# vcf_leiter.net
KiCad netlist of a schematic drawn in EAGLE
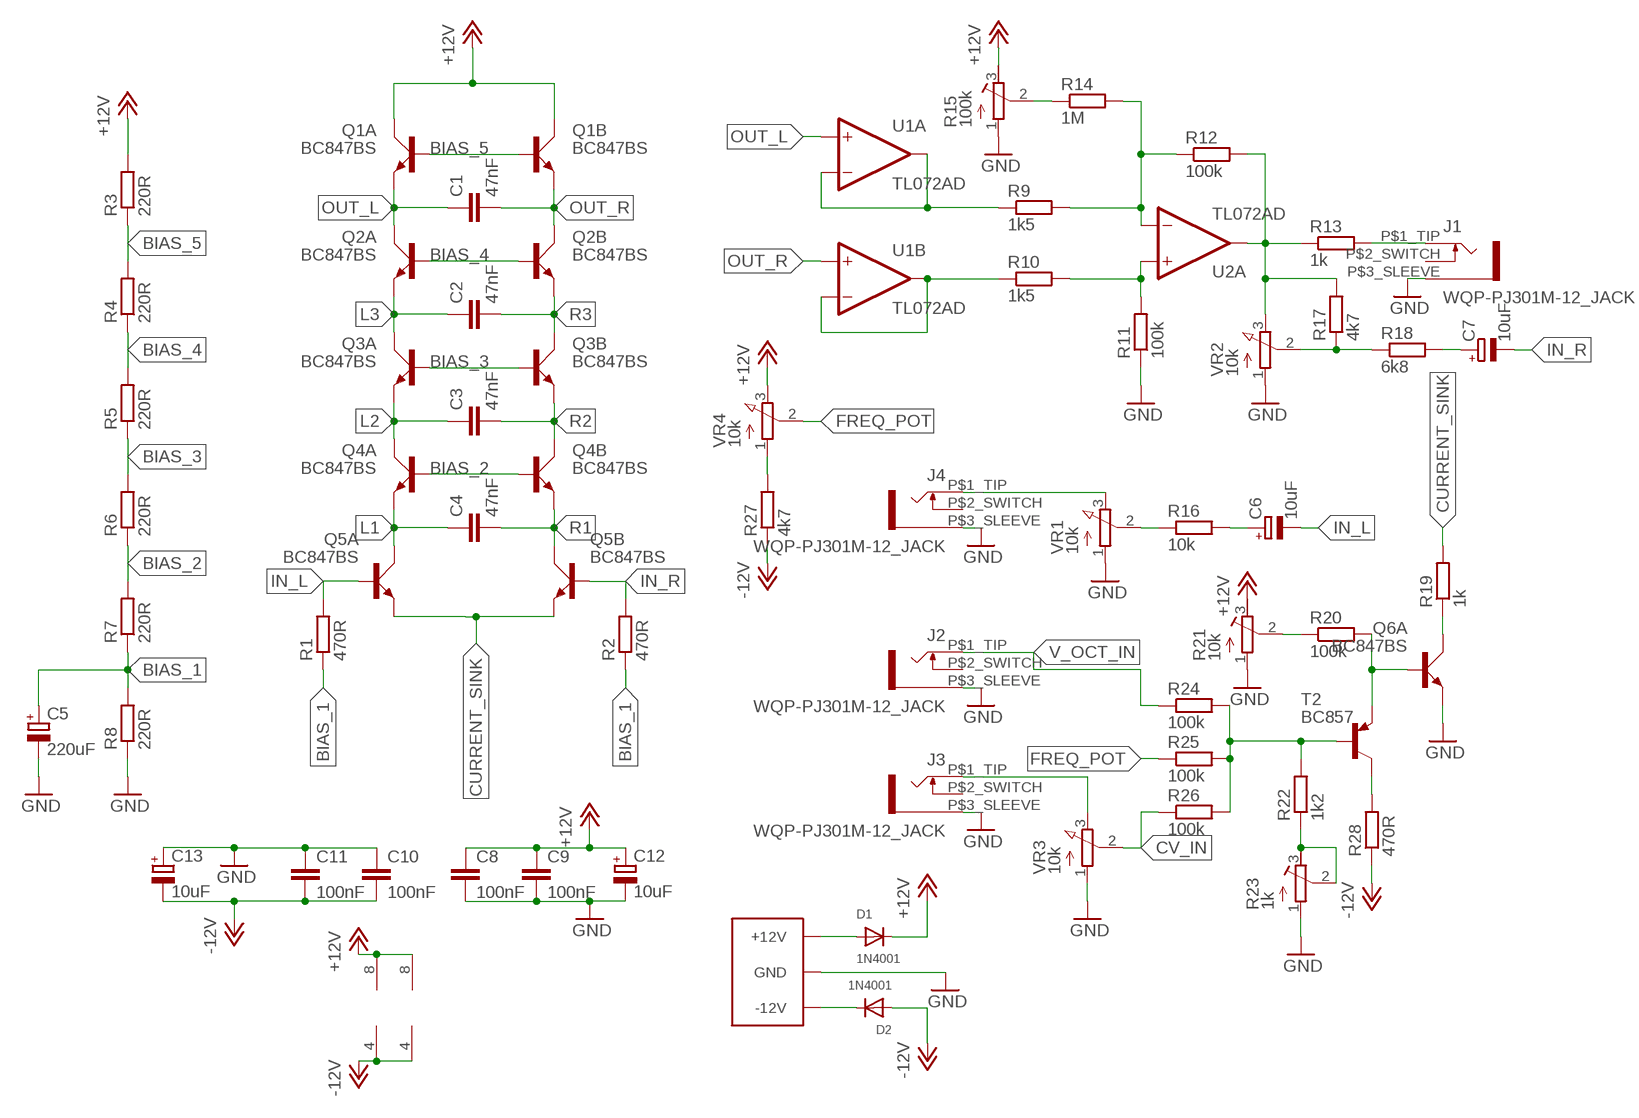
[diagram p0: schematic, sheet 1]

(export (version "E")
  (design (tool "Eeschema 10.0.6"))
  (components
    (comp (ref "C1")
      (value "47nF")
      (footprint "eagle-import:C0402")
      (libsource (lib "eagle-import") (part "C-EUC0402"))
    )
    (comp (ref "C2")
      (value "47nF")
      (footprint "eagle-import:C0402")
      (libsource (lib "eagle-import") (part "C-EUC0402"))
    )
    (comp (ref "C3")
      (value "47nF")
      (footprint "eagle-import:C0402")
      (libsource (lib "eagle-import") (part "C-EUC0402"))
    )
    (comp (ref "C4")
      (value "47nF")
      (footprint "eagle-import:C0402")
      (libsource (lib "eagle-import") (part "C-EUC0402"))
    )
    (comp (ref "C5")
      (value "220uF")
      (footprint "eagle-import:PANASONIC_C")
      (libsource (lib "eagle-import") (part "CPOL-EUC"))
    )
    (comp (ref "C6")
      (value "10uF")
      (footprint "eagle-import:PANASONIC_C")
      (libsource (lib "eagle-import") (part "CPOL-EUC"))
    )
    (comp (ref "C7")
      (value "10uF")
      (footprint "eagle-import:PANASONIC_C")
      (libsource (lib "eagle-import") (part "CPOL-EUC"))
    )
    (comp (ref "C8")
      (value "100nF")
      (footprint "eagle-import:C0402")
      (libsource (lib "eagle-import") (part "C-EUC0402"))
    )
    (comp (ref "C9")
      (value "100nF")
      (footprint "eagle-import:C0402")
      (libsource (lib "eagle-import") (part "C-EUC0402"))
    )
    (comp (ref "C10")
      (value "100nF")
      (footprint "eagle-import:C0402")
      (libsource (lib "eagle-import") (part "C-EUC0402"))
    )
    (comp (ref "C11")
      (value "100nF")
      (footprint "eagle-import:C0402")
      (libsource (lib "eagle-import") (part "C-EUC0402"))
    )
    (comp (ref "C12")
      (value "10uF")
      (footprint "eagle-import:PANASONIC_C")
      (libsource (lib "eagle-import") (part "CPOL-EUC"))
    )
    (comp (ref "C13")
      (value "10uF")
      (footprint "eagle-import:PANASONIC_C")
      (libsource (lib "eagle-import") (part "CPOL-EUC"))
    )
    (comp (ref "C14")
      (value "EURO_POWER_LOCKFAT-LOCK")
      (footprint "eagle-import:EURO_PWR_HEADER_LOCK")
      (libsource (lib "eagle-import") (part "EURO_POWER_LOCKFAT-LOCK"))
    )
    (comp (ref "D1")
      (value "1N4001")
      (footprint "eagle-import:SMADIODE")
      (libsource (lib "eagle-import") (part "DIODESMA"))
    )
    (comp (ref "D2")
      (value "1N4001")
      (footprint "eagle-import:SMADIODE")
      (libsource (lib "eagle-import") (part "DIODESMA"))
    )
    (comp (ref "J1")
      (value "WQP-PJ301M-12_JACK")
      (footprint "eagle-import:WQP-PJ301M-12_JACK")
      (libsource (lib "eagle-import") (part "WQP-PJ301M-12_JACK"))
    )
    (comp (ref "J2")
      (value "WQP-PJ301M-12_JACK")
      (footprint "eagle-import:WQP-PJ301M-12_JACK")
      (libsource (lib "eagle-import") (part "WQP-PJ301M-12_JACK"))
    )
    (comp (ref "J3")
      (value "WQP-PJ301M-12_JACK")
      (footprint "eagle-import:WQP-PJ301M-12_JACK")
      (libsource (lib "eagle-import") (part "WQP-PJ301M-12_JACK"))
    )
    (comp (ref "J4")
      (value "WQP-PJ301M-12_JACK")
      (footprint "eagle-import:WQP-PJ301M-12_JACK")
      (libsource (lib "eagle-import") (part "WQP-PJ301M-12_JACK"))
    )
    (comp (ref "Q1")
      (value "BC847BS")
      (footprint "eagle-import:SOT363_PHILIPS")
      (libsource (lib "eagle-import") (part "BC847BS"))
    )
    (comp (ref "Q2")
      (value "BC847BS")
      (footprint "eagle-import:SOT363_PHILIPS")
      (libsource (lib "eagle-import") (part "BC847BS"))
    )
    (comp (ref "Q3")
      (value "BC847BS")
      (footprint "eagle-import:SOT363_PHILIPS")
      (libsource (lib "eagle-import") (part "BC847BS"))
    )
    (comp (ref "Q4")
      (value "BC847BS")
      (footprint "eagle-import:SOT363_PHILIPS")
      (libsource (lib "eagle-import") (part "BC847BS"))
    )
    (comp (ref "Q5")
      (value "BC847BS")
      (footprint "eagle-import:SOT363_PHILIPS")
      (libsource (lib "eagle-import") (part "BC847BS"))
    )
    (comp (ref "Q6")
      (value "BC847BS")
      (footprint "eagle-import:SOT363_PHILIPS")
      (libsource (lib "eagle-import") (part "BC847BS"))
    )
    (comp (ref "R1")
      (value "470R")
      (footprint "eagle-import:R0402")
      (libsource (lib "eagle-import") (part "R-EU_R0402"))
    )
    (comp (ref "R2")
      (value "470R")
      (footprint "eagle-import:R0402")
      (libsource (lib "eagle-import") (part "R-EU_R0402"))
    )
    (comp (ref "R3")
      (value "220R")
      (footprint "eagle-import:R0402")
      (libsource (lib "eagle-import") (part "R-EU_R0402"))
    )
    (comp (ref "R4")
      (value "220R")
      (footprint "eagle-import:R0402")
      (libsource (lib "eagle-import") (part "R-EU_R0402"))
    )
    (comp (ref "R5")
      (value "220R")
      (footprint "eagle-import:R0402")
      (libsource (lib "eagle-import") (part "R-EU_R0402"))
    )
    (comp (ref "R6")
      (value "220R")
      (footprint "eagle-import:R0402")
      (libsource (lib "eagle-import") (part "R-EU_R0402"))
    )
    (comp (ref "R7")
      (value "220R")
      (footprint "eagle-import:R0402")
      (libsource (lib "eagle-import") (part "R-EU_R0402"))
    )
    (comp (ref "R8")
      (value "220R")
      (footprint "eagle-import:R0402")
      (libsource (lib "eagle-import") (part "R-EU_R0402"))
    )
    (comp (ref "R9")
      (value "1k5")
      (footprint "eagle-import:R0402")
      (libsource (lib "eagle-import") (part "R-EU_R0402"))
    )
    (comp (ref "R10")
      (value "1k5")
      (footprint "eagle-import:R0402")
      (libsource (lib "eagle-import") (part "R-EU_R0402"))
    )
    (comp (ref "R11")
      (value "100k")
      (footprint "eagle-import:R0402")
      (libsource (lib "eagle-import") (part "R-EU_R0402"))
    )
    (comp (ref "R12")
      (value "100k")
      (footprint "eagle-import:R0402")
      (libsource (lib "eagle-import") (part "R-EU_R0402"))
    )
    (comp (ref "R13")
      (value "1k")
      (footprint "eagle-import:R0402")
      (libsource (lib "eagle-import") (part "R-EU_R0402"))
    )
    (comp (ref "R14")
      (value "1M")
      (footprint "eagle-import:R0402")
      (libsource (lib "eagle-import") (part "R-EU_R0402"))
    )
    (comp (ref "R15")
      (value "100k")
      (footprint "eagle-import:RTRIM64W")
      (libsource (lib "eagle-import") (part "R-TRIMM64W"))
    )
    (comp (ref "R16")
      (value "10k")
      (footprint "eagle-import:R0402")
      (libsource (lib "eagle-import") (part "R-EU_R0402"))
    )
    (comp (ref "R17")
      (value "4k7")
      (footprint "eagle-import:R0402")
      (libsource (lib "eagle-import") (part "R-EU_R0402"))
    )
    (comp (ref "R18")
      (value "6k8")
      (footprint "eagle-import:R0402")
      (libsource (lib "eagle-import") (part "R-EU_R0402"))
    )
    (comp (ref "R19")
      (value "1k")
      (footprint "eagle-import:R0402")
      (libsource (lib "eagle-import") (part "R-EU_R0402"))
    )
    (comp (ref "R20")
      (value "100k")
      (footprint "eagle-import:R0402")
      (libsource (lib "eagle-import") (part "R-EU_R0402"))
    )
    (comp (ref "R21")
      (value "10k")
      (footprint "eagle-import:RTRIM64W")
      (libsource (lib "eagle-import") (part "R-TRIMM64W"))
    )
    (comp (ref "R22")
      (value "1k2")
      (footprint "eagle-import:R0402")
      (libsource (lib "eagle-import") (part "R-EU_R0402"))
    )
    (comp (ref "R23")
      (value "1k")
      (footprint "eagle-import:RTRIM64W")
      (libsource (lib "eagle-import") (part "R-TRIMM64W"))
    )
    (comp (ref "R24")
      (value "100k")
      (footprint "eagle-import:R0402")
      (libsource (lib "eagle-import") (part "R-EU_R0402"))
    )
    (comp (ref "R25")
      (value "100k")
      (footprint "eagle-import:R0402")
      (libsource (lib "eagle-import") (part "R-EU_R0402"))
    )
    (comp (ref "R26")
      (value "100k")
      (footprint "eagle-import:R0402")
      (libsource (lib "eagle-import") (part "R-EU_R0402"))
    )
    (comp (ref "R27")
      (value "4k7")
      (footprint "eagle-import:R0402")
      (libsource (lib "eagle-import") (part "R-EU_R0402"))
    )
    (comp (ref "R28")
      (value "470R")
      (footprint "eagle-import:R0402")
      (libsource (lib "eagle-import") (part "R-EU_R0402"))
    )
    (comp (ref "T2")
      (value "BC857")
      (footprint "eagle-import:SOT23-BEC")
      (libsource (lib "eagle-import") (part "-PNP-SOT23-BECBC857C"))
    )
    (comp (ref "U1")
      (value "TL072AD")
      (footprint "eagle-import:SOIC8")
      (libsource (lib "eagle-import") (part "TL072DA"))
    )
    (comp (ref "U2")
      (value "TL072AD")
      (footprint "eagle-import:SOIC8")
      (libsource (lib "eagle-import") (part "TL072DA"))
    )
    (comp (ref "VR1")
      (value "10k")
      (footprint "eagle-import:9MM_SNAP-IN_POT")
      (libsource (lib "eagle-import") (part "9MM_SNAP-IN_POT_"))
    )
    (comp (ref "VR2")
      (value "10k")
      (footprint "eagle-import:9MM_SNAP-IN_POT")
      (libsource (lib "eagle-import") (part "9MM_SNAP-IN_POT_"))
    )
    (comp (ref "VR3")
      (value "10k")
      (footprint "eagle-import:9MM_SNAP-IN_POT")
      (libsource (lib "eagle-import") (part "9MM_SNAP-IN_POT_"))
    )
    (comp (ref "VR4")
      (value "10k")
      (footprint "eagle-import:9MM_SNAP-IN_POT")
      (libsource (lib "eagle-import") (part "9MM_SNAP-IN_POT_"))
    )
  )
  (nets
    (net (code "1") (name "+12V") (class "Default")
      (node (ref "C12") (pin "+") (pinfunction "+_+") (pintype "passive"))
      (node (ref "C8") (pin "1") (pinfunction "1_1") (pintype "passive"))
      (node (ref "C9") (pin "1") (pinfunction "1_1") (pintype "passive"))
      (node (ref "D1") (pin "C") (pinfunction "C_C") (pintype "passive"))
      (node (ref "Q1") (pin "3") (pinfunction "C_3") (pintype "passive"))
      (node (ref "Q1") (pin "6") (pinfunction "C_6") (pintype "passive"))
      (node (ref "R15") (pin "3") (pinfunction "E_3") (pintype "passive"))
      (node (ref "R21") (pin "3") (pinfunction "E_3") (pintype "passive"))
      (node (ref "R3") (pin "2") (pinfunction "2_2") (pintype "passive"))
      (node (ref "U1") (pin "8") (pinfunction "V+_8") (pintype "power_in"))
      (node (ref "U2") (pin "8") (pinfunction "V+_8") (pintype "power_in"))
      (node (ref "VR4") (pin "3") (pinfunction "E_3") (pintype "passive"))
    )
    (net (code "2") (name "-12V") (class "Default")
      (node (ref "C10") (pin "2") (pinfunction "2_2") (pintype "passive"))
      (node (ref "C11") (pin "2") (pinfunction "2_2") (pintype "passive"))
      (node (ref "C13") (pin "-") (pinfunction "-_-") (pintype "passive"))
      (node (ref "D2") (pin "A") (pinfunction "A_A") (pintype "passive"))
      (node (ref "R27") (pin "1") (pinfunction "1_1") (pintype "passive"))
      (node (ref "R28") (pin "1") (pinfunction "1_1") (pintype "passive"))
      (node (ref "U1") (pin "4") (pinfunction "V-_4") (pintype "power_in"))
      (node (ref "U2") (pin "4") (pinfunction "V-_4") (pintype "power_in"))
    )
    (net (code "3") (name "BIAS_1") (class "Default")
      (node (ref "C5") (pin "+") (pinfunction "+_+") (pintype "passive"))
      (node (ref "R1") (pin "1") (pinfunction "1_1") (pintype "passive"))
      (node (ref "R2") (pin "1") (pinfunction "1_1") (pintype "passive"))
      (node (ref "R7") (pin "1") (pinfunction "1_1") (pintype "passive"))
      (node (ref "R8") (pin "2") (pinfunction "2_2") (pintype "passive"))
    )
    (net (code "4") (name "BIAS_2") (class "Default")
      (node (ref "Q4") (pin "2") (pinfunction "B_2") (pintype "passive"))
      (node (ref "Q4") (pin "5") (pinfunction "B_5") (pintype "passive"))
      (node (ref "R6") (pin "1") (pinfunction "1_1") (pintype "passive"))
      (node (ref "R7") (pin "2") (pinfunction "2_2") (pintype "passive"))
    )
    (net (code "5") (name "BIAS_3") (class "Default")
      (node (ref "Q3") (pin "2") (pinfunction "B_2") (pintype "passive"))
      (node (ref "Q3") (pin "5") (pinfunction "B_5") (pintype "passive"))
      (node (ref "R5") (pin "1") (pinfunction "1_1") (pintype "passive"))
      (node (ref "R6") (pin "2") (pinfunction "2_2") (pintype "passive"))
    )
    (net (code "6") (name "BIAS_4") (class "Default")
      (node (ref "Q2") (pin "2") (pinfunction "B_2") (pintype "passive"))
      (node (ref "Q2") (pin "5") (pinfunction "B_5") (pintype "passive"))
      (node (ref "R4") (pin "1") (pinfunction "1_1") (pintype "passive"))
      (node (ref "R5") (pin "2") (pinfunction "2_2") (pintype "passive"))
    )
    (net (code "7") (name "BIAS_5") (class "Default")
      (node (ref "Q1") (pin "2") (pinfunction "B_2") (pintype "passive"))
      (node (ref "Q1") (pin "5") (pinfunction "B_5") (pintype "passive"))
      (node (ref "R3") (pin "1") (pinfunction "1_1") (pintype "passive"))
      (node (ref "R4") (pin "2") (pinfunction "2_2") (pintype "passive"))
    )
    (net (code "8") (name "CURRENT_SINK") (class "Default")
      (node (ref "Q5") (pin "1") (pinfunction "E_1") (pintype "passive"))
      (node (ref "Q5") (pin "4") (pinfunction "E_4") (pintype "passive"))
      (node (ref "R19") (pin "2") (pinfunction "2_2") (pintype "passive"))
    )
    (net (code "9") (name "CV_IN") (class "Default")
      (node (ref "R26") (pin "1") (pinfunction "1_1") (pintype "passive"))
      (node (ref "VR3") (pin "2") (pinfunction "S_2") (pintype "passive"))
    )
    (net (code "10") (name "FREQ_POT") (class "Default")
      (node (ref "R25") (pin "1") (pinfunction "1_1") (pintype "passive"))
      (node (ref "VR4") (pin "2") (pinfunction "S_2") (pintype "passive"))
    )
    (net (code "11") (name "GND") (class "Default")
      (node (ref "C10") (pin "1") (pinfunction "1_1") (pintype "passive"))
      (node (ref "C11") (pin "1") (pinfunction "1_1") (pintype "passive"))
      (node (ref "C12") (pin "-") (pinfunction "-_-") (pintype "passive"))
      (node (ref "C13") (pin "+") (pinfunction "+_+") (pintype "passive"))
      (node (ref "C14") (pin "GND1") (pinfunction "GND_GND1") (pintype "bidirectional"))
      (node (ref "C14") (pin "GND2") (pinfunction "GND_GND2") (pintype "bidirectional"))
      (node (ref "C14") (pin "GND3") (pinfunction "GND_GND3") (pintype "bidirectional"))
      (node (ref "C14") (pin "GND4") (pinfunction "GND_GND4") (pintype "bidirectional"))
      (node (ref "C14") (pin "GND5") (pinfunction "GND_GND5") (pintype "bidirectional"))
      (node (ref "C14") (pin "GND6") (pinfunction "GND_GND6") (pintype "bidirectional"))
      (node (ref "C5") (pin "-") (pinfunction "-_-") (pintype "passive"))
      (node (ref "C8") (pin "2") (pinfunction "2_2") (pintype "passive"))
      (node (ref "C9") (pin "2") (pinfunction "2_2") (pintype "passive"))
      (node (ref "J1") (pin "P$3_SLEEVE") (pinfunction "1_P$3_SLEEVE") (pintype "passive"))
      (node (ref "J2") (pin "P$3_SLEEVE") (pinfunction "1_P$3_SLEEVE") (pintype "passive"))
      (node (ref "J3") (pin "P$3_SLEEVE") (pinfunction "1_P$3_SLEEVE") (pintype "passive"))
      (node (ref "J4") (pin "P$3_SLEEVE") (pinfunction "1_P$3_SLEEVE") (pintype "passive"))
      (node (ref "Q6") (pin "1") (pinfunction "E_1") (pintype "passive"))
      (node (ref "R11") (pin "1") (pinfunction "1_1") (pintype "passive"))
      (node (ref "R15") (pin "1") (pinfunction "A_1") (pintype "passive"))
      (node (ref "R21") (pin "1") (pinfunction "A_1") (pintype "passive"))
      (node (ref "R23") (pin "1") (pinfunction "A_1") (pintype "passive"))
      (node (ref "R8") (pin "1") (pinfunction "1_1") (pintype "passive"))
      (node (ref "VR1") (pin "1") (pinfunction "A_1") (pintype "passive"))
      (node (ref "VR2") (pin "1") (pinfunction "A_1") (pintype "passive"))
      (node (ref "VR3") (pin "1") (pinfunction "A_1") (pintype "passive"))
    )
    (net (code "12") (name "IN_L") (class "Default")
      (node (ref "C6") (pin "-") (pinfunction "-_-") (pintype "passive"))
      (node (ref "Q5") (pin "2") (pinfunction "B_2") (pintype "passive"))
      (node (ref "R1") (pin "2") (pinfunction "2_2") (pintype "passive"))
    )
    (net (code "13") (name "IN_R") (class "Default")
      (node (ref "C7") (pin "-") (pinfunction "-_-") (pintype "passive"))
      (node (ref "Q5") (pin "5") (pinfunction "B_5") (pintype "passive"))
      (node (ref "R2") (pin "2") (pinfunction "2_2") (pintype "passive"))
    )
    (net (code "14") (name "L1") (class "Default")
      (node (ref "C4") (pin "1") (pinfunction "1_1") (pintype "passive"))
      (node (ref "Q4") (pin "1") (pinfunction "E_1") (pintype "passive"))
      (node (ref "Q5") (pin "6") (pinfunction "C_6") (pintype "passive"))
    )
    (net (code "15") (name "L2") (class "Default")
      (node (ref "C3") (pin "1") (pinfunction "1_1") (pintype "passive"))
      (node (ref "Q3") (pin "1") (pinfunction "E_1") (pintype "passive"))
      (node (ref "Q4") (pin "6") (pinfunction "C_6") (pintype "passive"))
    )
    (net (code "16") (name "L3") (class "Default")
      (node (ref "C2") (pin "1") (pinfunction "1_1") (pintype "passive"))
      (node (ref "Q2") (pin "1") (pinfunction "E_1") (pintype "passive"))
      (node (ref "Q3") (pin "6") (pinfunction "C_6") (pintype "passive"))
    )
    (net (code "17") (name "Net-(C6-Pad+)") (class "Default")
      (node (ref "C6") (pin "+") (pinfunction "+_+") (pintype "passive"))
      (node (ref "R16") (pin "2") (pinfunction "2_2") (pintype "passive"))
    )
    (net (code "18") (name "Net-(C7-Pad+)") (class "Default")
      (node (ref "C7") (pin "+") (pinfunction "+_+") (pintype "passive"))
      (node (ref "R18") (pin "2") (pinfunction "2_2") (pintype "passive"))
    )
    (net (code "19") (name "Net-(C14-+12V-PadPOS1)") (class "Default")
      (node (ref "C14") (pin "POS1") (pinfunction "+12V_POS1") (pintype "bidirectional"))
      (node (ref "C14") (pin "POS2") (pinfunction "+12V_POS2") (pintype "bidirectional"))
      (node (ref "D1") (pin "A") (pinfunction "A_A") (pintype "passive"))
    )
    (net (code "20") (name "Net-(C14--12V-PadNEG1)") (class "Default")
      (node (ref "C14") (pin "NEG1") (pinfunction "-12V_NEG1") (pintype "bidirectional"))
      (node (ref "C14") (pin "NEG2") (pinfunction "-12V_NEG2") (pintype "bidirectional"))
      (node (ref "D2") (pin "C") (pinfunction "C_C") (pintype "passive"))
    )
    (net (code "21") (name "Net-(J1-2)") (class "Default")
      (node (ref "J1") (pin "P$1_TIP") (pinfunction "2_P$1_TIP") (pintype "passive"))
      (node (ref "R13") (pin "2") (pinfunction "2_2") (pintype "passive"))
    )
    (net (code "22") (name "Net-(J3-2)") (class "Default")
      (node (ref "J3") (pin "P$1_TIP") (pinfunction "2_P$1_TIP") (pintype "passive"))
      (node (ref "VR3") (pin "3") (pinfunction "E_3") (pintype "passive"))
    )
    (net (code "23") (name "Net-(J4-2)") (class "Default")
      (node (ref "J4") (pin "P$1_TIP") (pinfunction "2_P$1_TIP") (pintype "passive"))
      (node (ref "VR1") (pin "3") (pinfunction "E_3") (pintype "passive"))
    )
    (net (code "24") (name "Net-(Q6A-B)") (class "Default")
      (node (ref "Q6") (pin "2") (pinfunction "B_2") (pintype "passive"))
      (node (ref "R20") (pin "2") (pinfunction "2_2") (pintype "passive"))
      (node (ref "T2") (pin "E") (pinfunction "E_E") (pintype "passive"))
    )
    (net (code "25") (name "Net-(Q6A-C)") (class "Default")
      (node (ref "Q6") (pin "6") (pinfunction "C_6") (pintype "passive"))
      (node (ref "R19") (pin "1") (pinfunction "1_1") (pintype "passive"))
    )
    (net (code "26") (name "Net-(R15-S)") (class "Default")
      (node (ref "R14") (pin "1") (pinfunction "1_1") (pintype "passive"))
      (node (ref "R15") (pin "2") (pinfunction "S_2") (pintype "passive"))
    )
    (net (code "27") (name "Net-(R21-S)") (class "Default")
      (node (ref "R20") (pin "1") (pinfunction "1_1") (pintype "passive"))
      (node (ref "R21") (pin "2") (pinfunction "S_2") (pintype "passive"))
    )
    (net (code "28") (name "Net-(R22-Pad2)") (class "Default")
      (node (ref "R22") (pin "2") (pinfunction "2_2") (pintype "passive"))
      (node (ref "R24") (pin "2") (pinfunction "2_2") (pintype "passive"))
      (node (ref "R25") (pin "2") (pinfunction "2_2") (pintype "passive"))
      (node (ref "R26") (pin "2") (pinfunction "2_2") (pintype "passive"))
      (node (ref "T2") (pin "B") (pinfunction "B_B") (pintype "passive"))
    )
    (net (code "29") (name "Net-(R23-E)") (class "Default")
      (node (ref "R22") (pin "1") (pinfunction "1_1") (pintype "passive"))
      (node (ref "R23") (pin "2") (pinfunction "S_2") (pintype "passive"))
      (node (ref "R23") (pin "3") (pinfunction "E_3") (pintype "passive"))
    )
    (net (code "30") (name "Net-(R28-Pad2)") (class "Default")
      (node (ref "R28") (pin "2") (pinfunction "2_2") (pintype "passive"))
      (node (ref "T2") (pin "C") (pinfunction "C_C") (pintype "passive"))
    )
    (net (code "31") (name "Net-(U1A--IN)") (class "Default")
      (node (ref "R9") (pin "1") (pinfunction "1_1") (pintype "passive"))
      (node (ref "U1") (pin "1") (pinfunction "OUT_1") (pintype "output"))
      (node (ref "U1") (pin "2") (pinfunction "-IN_2") (pintype "input"))
    )
    (net (code "32") (name "Net-(U1B--IN)") (class "Default")
      (node (ref "R10") (pin "1") (pinfunction "1_1") (pintype "passive"))
      (node (ref "U1") (pin "6") (pinfunction "-IN_6") (pintype "input"))
      (node (ref "U1") (pin "7") (pinfunction "OUT_7") (pintype "output"))
    )
    (net (code "33") (name "Net-(U2A-+IN)") (class "Default")
      (node (ref "R10") (pin "2") (pinfunction "2_2") (pintype "passive"))
      (node (ref "R11") (pin "2") (pinfunction "2_2") (pintype "passive"))
      (node (ref "U2") (pin "3") (pinfunction "+IN_3") (pintype "input"))
    )
    (net (code "34") (name "Net-(U2A--IN)") (class "Default")
      (node (ref "R12") (pin "1") (pinfunction "1_1") (pintype "passive"))
      (node (ref "R14") (pin "2") (pinfunction "2_2") (pintype "passive"))
      (node (ref "R9") (pin "2") (pinfunction "2_2") (pintype "passive"))
      (node (ref "U2") (pin "2") (pinfunction "-IN_2") (pintype "input"))
    )
    (net (code "35") (name "Net-(U2A-OUT)") (class "Default")
      (node (ref "R12") (pin "2") (pinfunction "2_2") (pintype "passive"))
      (node (ref "R13") (pin "1") (pinfunction "1_1") (pintype "passive"))
      (node (ref "R17") (pin "2") (pinfunction "2_2") (pintype "passive"))
      (node (ref "U2") (pin "1") (pinfunction "OUT_1") (pintype "output"))
      (node (ref "VR2") (pin "3") (pinfunction "E_3") (pintype "passive"))
    )
    (net (code "36") (name "Net-(VR1-S)") (class "Default")
      (node (ref "R16") (pin "1") (pinfunction "1_1") (pintype "passive"))
      (node (ref "VR1") (pin "2") (pinfunction "S_2") (pintype "passive"))
    )
    (net (code "37") (name "Net-(VR2-S)") (class "Default")
      (node (ref "R17") (pin "1") (pinfunction "1_1") (pintype "passive"))
      (node (ref "R18") (pin "1") (pinfunction "1_1") (pintype "passive"))
      (node (ref "VR2") (pin "2") (pinfunction "S_2") (pintype "passive"))
    )
    (net (code "38") (name "Net-(VR4-A)") (class "Default")
      (node (ref "R27") (pin "2") (pinfunction "2_2") (pintype "passive"))
      (node (ref "VR4") (pin "1") (pinfunction "A_1") (pintype "passive"))
    )
    (net (code "39") (name "OUT_L") (class "Default")
      (node (ref "C1") (pin "1") (pinfunction "1_1") (pintype "passive"))
      (node (ref "Q1") (pin "1") (pinfunction "E_1") (pintype "passive"))
      (node (ref "Q2") (pin "6") (pinfunction "C_6") (pintype "passive"))
      (node (ref "U1") (pin "3") (pinfunction "+IN_3") (pintype "input"))
    )
    (net (code "40") (name "OUT_R") (class "Default")
      (node (ref "C1") (pin "2") (pinfunction "2_2") (pintype "passive"))
      (node (ref "Q1") (pin "4") (pinfunction "E_4") (pintype "passive"))
      (node (ref "Q2") (pin "3") (pinfunction "C_3") (pintype "passive"))
      (node (ref "U1") (pin "5") (pinfunction "+IN_5") (pintype "input"))
    )
    (net (code "41") (name "R1") (class "Default")
      (node (ref "C4") (pin "2") (pinfunction "2_2") (pintype "passive"))
      (node (ref "Q4") (pin "4") (pinfunction "E_4") (pintype "passive"))
      (node (ref "Q5") (pin "3") (pinfunction "C_3") (pintype "passive"))
    )
    (net (code "42") (name "R2") (class "Default")
      (node (ref "C3") (pin "2") (pinfunction "2_2") (pintype "passive"))
      (node (ref "Q3") (pin "4") (pinfunction "E_4") (pintype "passive"))
      (node (ref "Q4") (pin "3") (pinfunction "C_3") (pintype "passive"))
    )
    (net (code "43") (name "R3") (class "Default")
      (node (ref "C2") (pin "2") (pinfunction "2_2") (pintype "passive"))
      (node (ref "Q2") (pin "4") (pinfunction "E_4") (pintype "passive"))
      (node (ref "Q3") (pin "3") (pinfunction "C_3") (pintype "passive"))
    )
    (net (code "44") (name "V_OCT_IN") (class "Default")
      (node (ref "J2") (pin "P$1_TIP") (pinfunction "2_P$1_TIP") (pintype "passive"))
      (node (ref "R24") (pin "1") (pinfunction "1_1") (pintype "passive"))
    )
    (net (code "45") (name "unconnected-(J1-3-PadP$2_SWITCH)") (class "Default")
      (node (ref "J1") (pin "P$2_SWITCH") (pinfunction "3_P$2_SWITCH") (pintype "passive"))
    )
    (net (code "46") (name "unconnected-(J2-3-PadP$2_SWITCH)") (class "Default")
      (node (ref "J2") (pin "P$2_SWITCH") (pinfunction "3_P$2_SWITCH") (pintype "passive"))
    )
    (net (code "47") (name "unconnected-(J3-3-PadP$2_SWITCH)") (class "Default")
      (node (ref "J3") (pin "P$2_SWITCH") (pinfunction "3_P$2_SWITCH") (pintype "passive"))
    )
    (net (code "48") (name "unconnected-(J4-3-PadP$2_SWITCH)") (class "Default")
      (node (ref "J4") (pin "P$2_SWITCH") (pinfunction "3_P$2_SWITCH") (pintype "passive"))
    )
  )
)
